# FireflyRevB.net
KiCad netlist of a schematic drawn in EAGLE
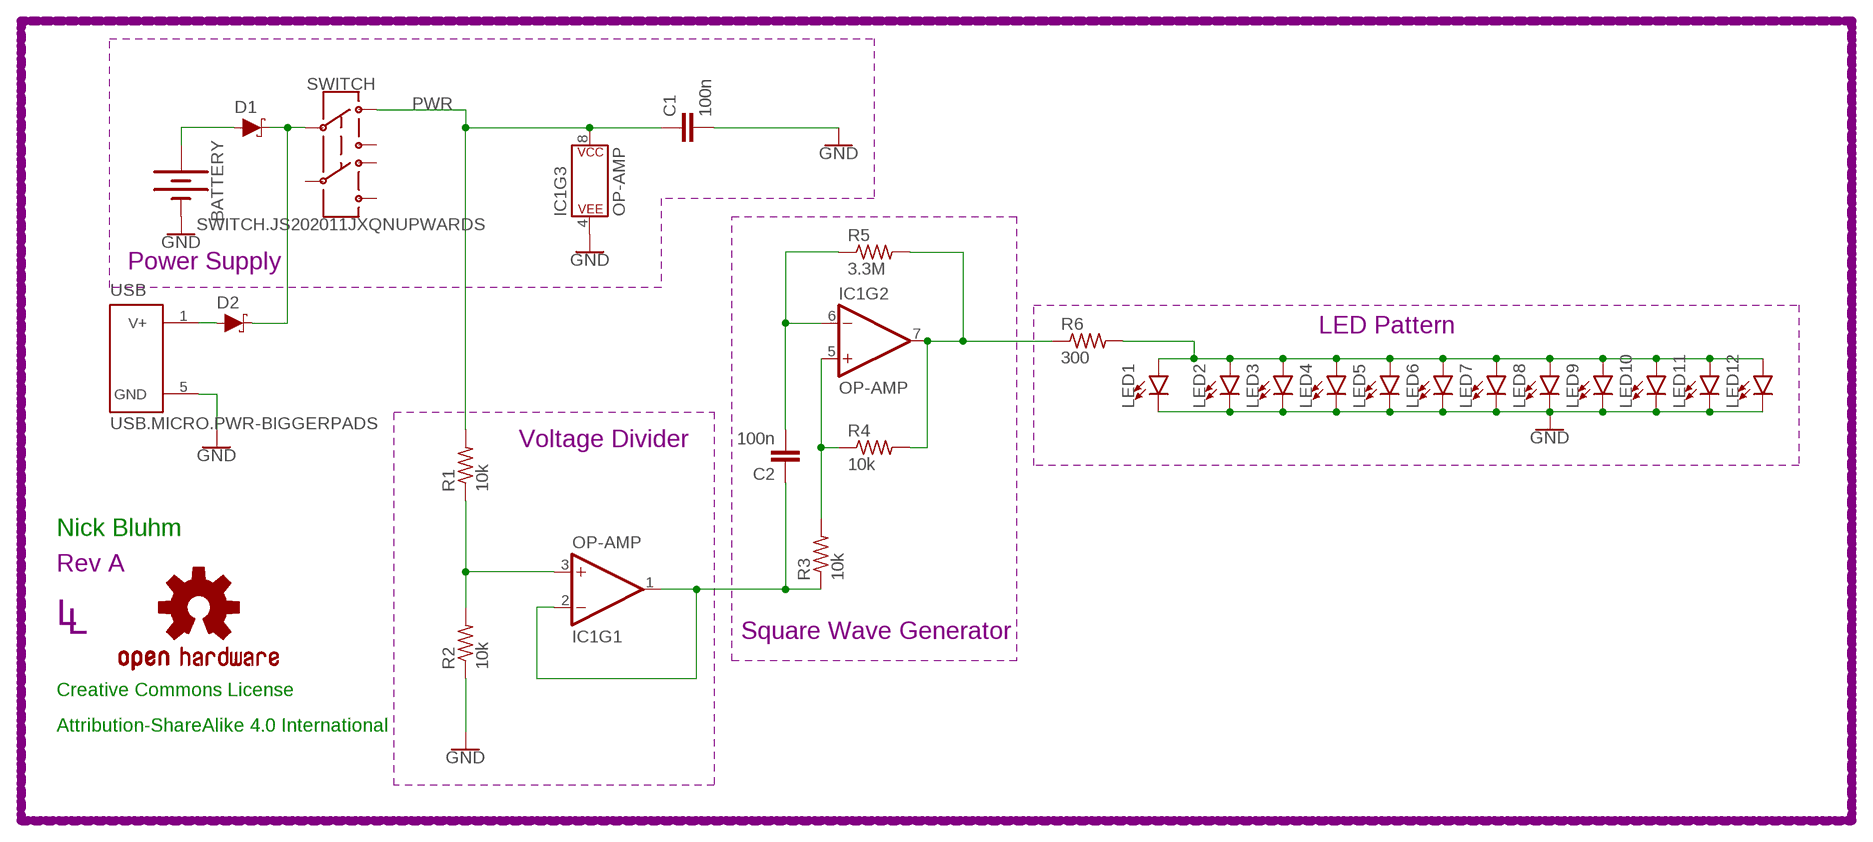
[diagram p0: schematic, sheet 1]

(export (version "E")
  (design (tool "Eeschema 10.0.6"))
  (components
    (comp (ref "BATTERY")
      (value "BATTERY-20MM_SMD")
      (footprint "eagle-import:BATTCON_20MM")
      (libsource (lib "eagle-import") (part "BATTERY-20MM_SMD"))
    )
    (comp (ref "C1")
      (value "100n")
      (footprint "eagle-import:C0603")
      (libsource (lib "eagle-import") (part "CAPACITOR0603"))
    )
    (comp (ref "C2")
      (value "100n")
      (footprint "eagle-import:C0603")
      (libsource (lib "eagle-import") (part "CAPACITOR0603"))
    )
    (comp (ref "D1")
      (value "SCHOTTKY-USC")
      (footprint "eagle-import:USC")
      (libsource (lib "eagle-import") (part "SCHOTTKY-USC"))
    )
    (comp (ref "D2")
      (value "SCHOTTKY-USC")
      (footprint "eagle-import:USC")
      (libsource (lib "eagle-import") (part "SCHOTTKY-USC"))
    )
    (comp (ref "IC1")
      (value "OP-AMP")
      (footprint "eagle-import:SO08")
      (libsource (lib "eagle-import") (part "OPAMP-DUALU"))
    )
    (comp (ref "LED1")
      (value "LED5MM")
      (footprint "eagle-import:LED_5MM")
      (libsource (lib "eagle-import") (part "LED5MM"))
    )
    (comp (ref "LED2")
      (value "LED5MM")
      (footprint "eagle-import:LED_5MM")
      (libsource (lib "eagle-import") (part "LED5MM"))
    )
    (comp (ref "LED3")
      (value "LED5MM")
      (footprint "eagle-import:LED_5MM")
      (libsource (lib "eagle-import") (part "LED5MM"))
    )
    (comp (ref "LED4")
      (value "LED5MM")
      (footprint "eagle-import:LED_5MM")
      (libsource (lib "eagle-import") (part "LED5MM"))
    )
    (comp (ref "LED5")
      (value "LED5MM")
      (footprint "eagle-import:LED_5MM")
      (libsource (lib "eagle-import") (part "LED5MM"))
    )
    (comp (ref "LED6")
      (value "LED5MM")
      (footprint "eagle-import:LED_5MM")
      (libsource (lib "eagle-import") (part "LED5MM"))
    )
    (comp (ref "LED7")
      (value "LED5MM")
      (footprint "eagle-import:LED_5MM")
      (libsource (lib "eagle-import") (part "LED5MM"))
    )
    (comp (ref "LED8")
      (value "LED5MM")
      (footprint "eagle-import:LED_5MM")
      (libsource (lib "eagle-import") (part "LED5MM"))
    )
    (comp (ref "LED9")
      (value "LED5MM")
      (footprint "eagle-import:LED_5MM")
      (libsource (lib "eagle-import") (part "LED5MM"))
    )
    (comp (ref "LED10")
      (value "LED5MM")
      (footprint "eagle-import:LED_5MM")
      (libsource (lib "eagle-import") (part "LED5MM"))
    )
    (comp (ref "LED11")
      (value "LED5MM")
      (footprint "eagle-import:LED_5MM")
      (libsource (lib "eagle-import") (part "LED5MM"))
    )
    (comp (ref "LED12")
      (value "LED5MM")
      (footprint "eagle-import:LED_5MM")
      (libsource (lib "eagle-import") (part "LED5MM"))
    )
    (comp (ref "LOGO1")
      (value "OSHW-LOGOL-COPPER")
      (footprint "eagle-import:OSHW-LOGO-L_COPPER")
      (libsource (lib "eagle-import") (part "OSHW-LOGOL-COPPER"))
    )
    (comp (ref "R1")
      (value "10k")
      (footprint "eagle-import:R0603")
      (libsource (lib "eagle-import") (part "RESISTOR0603"))
    )
    (comp (ref "R2")
      (value "10k")
      (footprint "eagle-import:R0603")
      (libsource (lib "eagle-import") (part "RESISTOR0603"))
    )
    (comp (ref "R3")
      (value "10k")
      (footprint "eagle-import:R0603")
      (libsource (lib "eagle-import") (part "RESISTOR0603"))
    )
    (comp (ref "R4")
      (value "10k")
      (footprint "eagle-import:R0603")
      (libsource (lib "eagle-import") (part "RESISTOR0603"))
    )
    (comp (ref "R5")
      (value "3.3M")
      (footprint "eagle-import:R0603")
      (libsource (lib "eagle-import") (part "RESISTOR0603"))
    )
    (comp (ref "R6")
      (value "300")
      (footprint "eagle-import:R0603")
      (libsource (lib "eagle-import") (part "RESISTOR0603"))
    )
    (comp (ref "SWITCH")
      (value "SWITCH.JS202011JXQNUPWARDS")
      (footprint "eagle-import:SWITCH.00")
      (libsource (lib "eagle-import") (part "SWITCH.JS202011JXQNUPWARDS"))
    )
    (comp (ref "U$4")
      (value "REVISION.A")
      (footprint "eagle-import:REV.A")
      (libsource (lib "eagle-import") (part "REVISION.A"))
    )
    (comp (ref "U$5")
      (value "LINNES.LAB.LOGO")
      (footprint "eagle-import:LINNES.LAB.LOGO")
      (libsource (lib "eagle-import") (part "LINNES.LAB.LOGO"))
    )
    (comp (ref "USB")
      (value "USB.MICRO.PWR-BIGGERPADS")
      (footprint "eagle-import:USB-MICRO-01.BIGGERPADS.PWR")
      (libsource (lib "eagle-import") (part "USB.MICRO.PWR-BIGGERPADS"))
    )
  )
  (nets
    (net (code "1") (name "/PWR") (class "Default")
      (node (ref "C1") (pin "1") (pinfunction "1_1") (pintype "passive"))
      (node (ref "IC1") (pin "8") (pinfunction "P$V+_8") (pintype "bidirectional"))
      (node (ref "R1") (pin "2") (pinfunction "2_2") (pintype "passive"))
      (node (ref "SWITCH") (pin "1") (pinfunction "1_1") (pintype "bidirectional"))
    )
    (net (code "2") (name "GND") (class "Default")
      (node (ref "BATTERY") (pin "2") (pinfunction "-_2") (pintype "power_in"))
      (node (ref "C1") (pin "2") (pinfunction "2_2") (pintype "passive"))
      (node (ref "IC1") (pin "4") (pinfunction "P$V-_4") (pintype "bidirectional"))
      (node (ref "LED1") (pin "K") (pinfunction "C_K") (pintype "passive"))
      (node (ref "LED10") (pin "K") (pinfunction "C_K") (pintype "passive"))
      (node (ref "LED11") (pin "K") (pinfunction "C_K") (pintype "passive"))
      (node (ref "LED12") (pin "K") (pinfunction "C_K") (pintype "passive"))
      (node (ref "LED2") (pin "K") (pinfunction "C_K") (pintype "passive"))
      (node (ref "LED3") (pin "K") (pinfunction "C_K") (pintype "passive"))
      (node (ref "LED4") (pin "K") (pinfunction "C_K") (pintype "passive"))
      (node (ref "LED5") (pin "K") (pinfunction "C_K") (pintype "passive"))
      (node (ref "LED6") (pin "K") (pinfunction "C_K") (pintype "passive"))
      (node (ref "LED7") (pin "K") (pinfunction "C_K") (pintype "passive"))
      (node (ref "LED8") (pin "K") (pinfunction "C_K") (pintype "passive"))
      (node (ref "LED9") (pin "K") (pinfunction "C_K") (pintype "passive"))
      (node (ref "R2") (pin "1") (pinfunction "1_1") (pintype "passive"))
      (node (ref "USB") (pin "5") (pinfunction "GND_5") (pintype "bidirectional"))
    )
    (net (code "3") (name "Net-(BATTERY-+)") (class "Default")
      (node (ref "BATTERY") (pin "1") (pinfunction "+_1") (pintype "power_in"))
      (node (ref "D1") (pin "+") (pinfunction "A_+") (pintype "passive"))
    )
    (net (code "4") (name "Net-(D1-C)") (class "Default")
      (node (ref "D1") (pin "-") (pinfunction "C_-") (pintype "passive"))
      (node (ref "D2") (pin "-") (pinfunction "C_-") (pintype "passive"))
      (node (ref "SWITCH") (pin "2") (pinfunction "2_2") (pintype "bidirectional"))
    )
    (net (code "5") (name "Net-(D2-A)") (class "Default")
      (node (ref "D2") (pin "+") (pinfunction "A_+") (pintype "passive"))
      (node (ref "USB") (pin "1") (pinfunction "V+_1") (pintype "bidirectional"))
    )
    (net (code "6") (name "Net-(IC1A-+IN)") (class "Default")
      (node (ref "IC1") (pin "3") (pinfunction "+IN_3") (pintype "input"))
      (node (ref "R1") (pin "1") (pinfunction "1_1") (pintype "passive"))
      (node (ref "R2") (pin "2") (pinfunction "2_2") (pintype "passive"))
    )
    (net (code "7") (name "Net-(IC1A--IN)") (class "Default")
      (node (ref "C2") (pin "1") (pinfunction "1_1") (pintype "passive"))
      (node (ref "IC1") (pin "1") (pinfunction "OUT_1") (pintype "output"))
      (node (ref "IC1") (pin "2") (pinfunction "-IN_2") (pintype "input"))
      (node (ref "R3") (pin "1") (pinfunction "1_1") (pintype "passive"))
    )
    (net (code "8") (name "Net-(IC1B-+IN)") (class "Default")
      (node (ref "IC1") (pin "5") (pinfunction "+IN_5") (pintype "input"))
      (node (ref "R3") (pin "2") (pinfunction "2_2") (pintype "passive"))
      (node (ref "R4") (pin "1") (pinfunction "1_1") (pintype "passive"))
    )
    (net (code "9") (name "Net-(IC1B--IN)") (class "Default")
      (node (ref "C2") (pin "2") (pinfunction "2_2") (pintype "passive"))
      (node (ref "IC1") (pin "6") (pinfunction "-IN_6") (pintype "input"))
      (node (ref "R5") (pin "1") (pinfunction "1_1") (pintype "passive"))
    )
    (net (code "10") (name "Net-(IC1B-OUT)") (class "Default")
      (node (ref "IC1") (pin "7") (pinfunction "OUT_7") (pintype "output"))
      (node (ref "R4") (pin "2") (pinfunction "2_2") (pintype "passive"))
      (node (ref "R5") (pin "2") (pinfunction "2_2") (pintype "passive"))
      (node (ref "R6") (pin "1") (pinfunction "1_1") (pintype "passive"))
    )
    (net (code "11") (name "Net-(LED1-PadA)") (class "Default")
      (node (ref "LED1") (pin "A") (pinfunction "A_A") (pintype "passive"))
      (node (ref "LED10") (pin "A") (pinfunction "A_A") (pintype "passive"))
      (node (ref "LED11") (pin "A") (pinfunction "A_A") (pintype "passive"))
      (node (ref "LED12") (pin "A") (pinfunction "A_A") (pintype "passive"))
      (node (ref "LED2") (pin "A") (pinfunction "A_A") (pintype "passive"))
      (node (ref "LED3") (pin "A") (pinfunction "A_A") (pintype "passive"))
      (node (ref "LED4") (pin "A") (pinfunction "A_A") (pintype "passive"))
      (node (ref "LED5") (pin "A") (pinfunction "A_A") (pintype "passive"))
      (node (ref "LED6") (pin "A") (pinfunction "A_A") (pintype "passive"))
      (node (ref "LED7") (pin "A") (pinfunction "A_A") (pintype "passive"))
      (node (ref "LED8") (pin "A") (pinfunction "A_A") (pintype "passive"))
      (node (ref "LED9") (pin "A") (pinfunction "A_A") (pintype "passive"))
      (node (ref "R6") (pin "2") (pinfunction "2_2") (pintype "passive"))
    )
    (net (code "12") (name "unconnected-(SWITCH-Pad3)") (class "Default")
      (node (ref "SWITCH") (pin "3") (pinfunction "3_3") (pintype "bidirectional"))
    )
    (net (code "13") (name "unconnected-(SWITCH-Pad5)") (class "Default")
      (node (ref "SWITCH") (pin "5") (pinfunction "5_5") (pintype "bidirectional"))
    )
    (net (code "14") (name "unconnected-(SWITCH-Pad6)") (class "Default")
      (node (ref "SWITCH") (pin "6") (pinfunction "6_6") (pintype "bidirectional"))
    )
    (net (code "15") (name "unconnected-(SWITCH-Pad7)") (class "Default")
      (node (ref "SWITCH") (pin "7") (pinfunction "7_7") (pintype "bidirectional"))
    )
  )
)
